# interface.net
KiCad netlist of a schematic drawn in Altium Designer
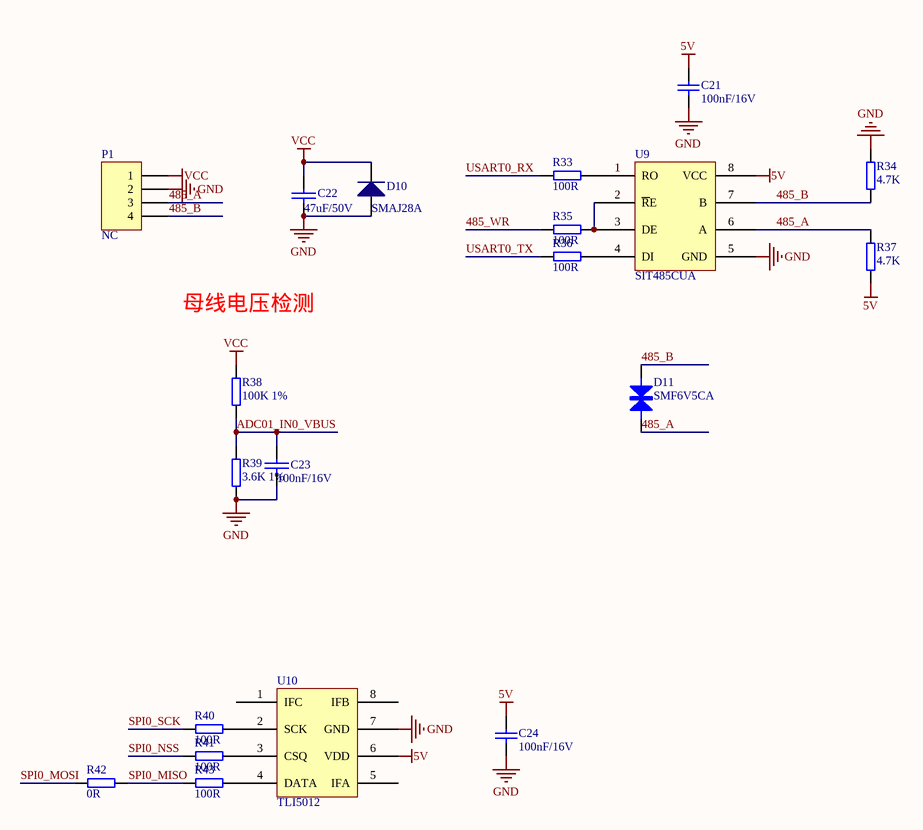
[diagram p0: interface.SchDoc]

(export (version "E")
  (design (tool "Eeschema 10.0.6"))
  (components
    (comp (ref "C21") (value "100nF/16V") (footprint "C0402") (libsource (lib "zijianku") (part "cap")))
    (comp (ref "C22")
      (value "47uF/50V")
      (footprint "C1210_N")
      (description "Capacitor")
      (libsource (lib "*") (part "CAP"))
    )
    (comp (ref "C23")
      (value "100nF/16V")
      (footprint "C0402")
      (description "Capacitor")
      (libsource (lib "*") (part "CAP"))
    )
    (comp (ref "C24") (value "100nF/16V") (footprint "C0402") (libsource (lib "zijianku") (part "cap")))
    (comp (ref "D10")
      (value "SMAJ28A")
      (footprint "DO-214AC SMA")
      (libsource (lib "Common Device") (part "Diode"))
    )
    (comp (ref "D11")
      (value "SMF6V5CA")
      (footprint "SOD-123")
      (libsource (lib "zijianku") (part "Bi-DIODES"))
    )
    (comp (ref "P1")
      (value "NC")
      (footprint "2.54-4")
      (fields (field (name "PUBLISHER") "Altium Limited"))
      (libsource (lib "Common Headers") (part "Header 4"))
    )
    (comp (ref "R33") (value "100R") (footprint "R0402") (libsource (lib "zijianku") (part "Resistance")))
    (comp (ref "R34") (value "4.7K") (footprint "R0402") (libsource (lib "zijianku") (part "Resistance")))
    (comp (ref "R35") (value "100R") (footprint "R0402") (libsource (lib "zijianku") (part "Resistance")))
    (comp (ref "R36") (value "100R") (footprint "R0402") (libsource (lib "zijianku") (part "Resistance")))
    (comp (ref "R37") (value "4.7K") (footprint "R0402") (libsource (lib "zijianku") (part "Resistance")))
    (comp (ref "R38") (value "100K 1%") (footprint "R0402") (libsource (lib "zijianku") (part "Resistance")))
    (comp (ref "R39") (value "3.6K 1%") (footprint "R0402") (libsource (lib "zijianku") (part "Resistance")))
    (comp (ref "R40") (value "100R") (footprint "R0402") (libsource (lib "zijianku") (part "Resistance")))
    (comp (ref "R41") (value "100R") (footprint "R0402") (libsource (lib "zijianku") (part "Resistance")))
    (comp (ref "R42") (value "0R") (footprint "R0402") (libsource (lib "zijianku") (part "Resistance")))
    (comp (ref "R43") (value "100R") (footprint "R0402") (libsource (lib "zijianku") (part "Resistance")))
    (comp (ref "U9")
      (value "SIT485CUA")
      (footprint "VSSOP/MSOP-8")
      (libsource (lib "zijianku") (part "SP485"))
    )
    (comp (ref "U10") (value "TLI5012") (footprint "SOIC-8") (libsource (lib "zijianku") (part "TLE5012")))
  )
  (nets
    (net (code "1") (name "/485_A") (class "Default")
      (node (ref "D11") (pin "2") (pinfunction "Anode_2") (pintype "passive"))
      (node (ref "P1") (pin "3") (pinfunction "3_3") (pintype "passive"))
      (node (ref "R37") (pin "2") (pintype "passive"))
      (node (ref "U9") (pin "6") (pinfunction "A_6") (pintype "passive"))
    )
    (net (code "2") (name "/485_B") (class "Default")
      (node (ref "D11") (pin "1") (pinfunction "Anode_1") (pintype "passive"))
      (node (ref "P1") (pin "4") (pinfunction "4_4") (pintype "passive"))
      (node (ref "R34") (pin "1") (pintype "passive"))
      (node (ref "U9") (pin "7") (pinfunction "B_7") (pintype "passive"))
    )
    (net (code "3") (name "/485_WR") (class "Default") (node (ref "R35") (pin "2") (pintype "passive")))
    (net (code "4") (name "/ADC01_IN0_VBUS") (class "Default")
      (node (ref "C23") (pin "1") (pinfunction "1_1") (pintype "passive"))
      (node (ref "R38") (pin "1") (pintype "passive"))
      (node (ref "R39") (pin "2") (pintype "passive"))
    )
    (net (code "5") (name "/SPI0_MISO") (class "Default")
      (node (ref "R42") (pin "1") (pintype "passive"))
      (node (ref "R43") (pin "2") (pintype "passive"))
    )
    (net (code "6") (name "/SPI0_MOSI") (class "Default") (node (ref "R42") (pin "2") (pintype "passive")))
    (net (code "7") (name "/SPI0_NSS") (class "Default") (node (ref "R41") (pin "2") (pintype "passive")))
    (net (code "8") (name "/SPI0_SCK") (class "Default") (node (ref "R40") (pin "2") (pintype "passive")))
    (net (code "9") (name "/USART0_RX") (class "Default") (node (ref "R33") (pin "2") (pintype "passive")))
    (net (code "10") (name "/USART0_TX") (class "Default") (node (ref "R36") (pin "2") (pintype "passive")))
    (net (code "11") (name "5V") (class "Default")
      (node (ref "C21") (pin "1") (pinfunction "0_1") (pintype "passive"))
      (node (ref "C24") (pin "1") (pinfunction "0_1") (pintype "passive"))
      (node (ref "R37") (pin "1") (pintype "passive"))
      (node (ref "U10") (pin "6") (pinfunction "VDD_6") (pintype "passive"))
      (node (ref "U9") (pin "8") (pinfunction "VCC_8") (pintype "passive"))
    )
    (net (code "12") (name "GND") (class "Default")
      (node (ref "C21") (pin "2") (pinfunction "1_2") (pintype "passive"))
      (node (ref "C22") (pin "2") (pinfunction "2_2") (pintype "passive"))
      (node (ref "C23") (pin "2") (pinfunction "2_2") (pintype "passive"))
      (node (ref "C24") (pin "2") (pinfunction "1_2") (pintype "passive"))
      (node (ref "D10") (pin "1") (pinfunction "0_1") (pintype "passive"))
      (node (ref "P1") (pin "2") (pinfunction "2_2") (pintype "passive"))
      (node (ref "R34") (pin "2") (pintype "passive"))
      (node (ref "R39") (pin "1") (pintype "passive"))
      (node (ref "U10") (pin "7") (pinfunction "GND_7") (pintype "passive"))
      (node (ref "U9") (pin "5") (pinfunction "GND_5") (pintype "passive"))
    )
    (net (code "13") (name "Net-(U9-DE)") (class "Default")
      (node (ref "R35") (pin "1") (pintype "passive"))
      (node (ref "U9") (pin "2") (pinfunction "~{R}E_2") (pintype "passive"))
      (node (ref "U9") (pin "3") (pinfunction "DE_3") (pintype "passive"))
    )
    (net (code "14") (name "Net-(U9-DI)") (class "Default")
      (node (ref "R36") (pin "1") (pintype "passive"))
      (node (ref "U9") (pin "4") (pinfunction "DI_4") (pintype "passive"))
    )
    (net (code "15") (name "Net-(U9-RO)") (class "Default")
      (node (ref "R33") (pin "1") (pintype "passive"))
      (node (ref "U9") (pin "1") (pinfunction "RO_1") (pintype "passive"))
    )
    (net (code "16") (name "Net-(U10-CSQ)") (class "Default")
      (node (ref "R41") (pin "1") (pintype "passive"))
      (node (ref "U10") (pin "3") (pinfunction "CSQ_3") (pintype "passive"))
    )
    (net (code "17") (name "Net-(U10-DATA)") (class "Default")
      (node (ref "R43") (pin "1") (pintype "passive"))
      (node (ref "U10") (pin "4") (pinfunction "DATA_4") (pintype "passive"))
    )
    (net (code "18") (name "Net-(U10-SCK)") (class "Default")
      (node (ref "R40") (pin "1") (pintype "passive"))
      (node (ref "U10") (pin "2") (pinfunction "SCK_2") (pintype "passive"))
    )
    (net (code "19") (name "VCC") (class "Default")
      (node (ref "C22") (pin "1") (pinfunction "1_1") (pintype "passive"))
      (node (ref "D10") (pin "2") (pinfunction "1_2") (pintype "passive"))
      (node (ref "P1") (pin "1") (pinfunction "1_1") (pintype "passive"))
      (node (ref "R38") (pin "2") (pintype "passive"))
    )
    (net (code "20") (name "unconnected-(U10-IFA-Pad5)") (class "Default")
      (node (ref "U10") (pin "5") (pinfunction "IFA_5") (pintype "passive"))
    )
    (net (code "21") (name "unconnected-(U10-IFB-Pad8)") (class "Default")
      (node (ref "U10") (pin "8") (pinfunction "IFB_8") (pintype "passive"))
    )
    (net (code "22") (name "unconnected-(U10-IFC-Pad1)") (class "Default")
      (node (ref "U10") (pin "1") (pinfunction "IFC_1") (pintype "passive"))
    )
  )
)
